# PowerSupplies.net
KiCad netlist of a schematic drawn in Altium Designer
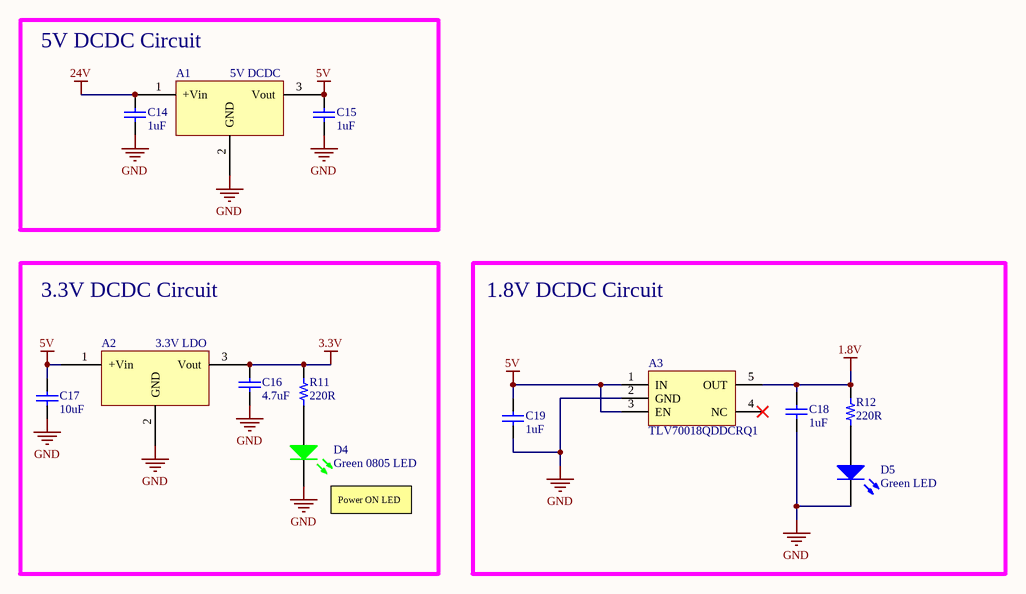
[diagram p0: PowerSupplies.SchDoc]

(export (version "E")
  (design (tool "Eeschema 10.0.6"))
  (components
    (comp (ref "A1")
      (value "5V DCDC")
      (footprint "R-78E-0.5")
      (fields (field (name "MANUFACTURER") "Recom") (field (name "PART_NUMBER") "R-78E5.0-0.5"))
      (libsource (lib "Other") (part "R78E5.0-0.5"))
    )
    (comp (ref "A2")
      (value "3.3V LDO")
      (footprint "TO252-3")
      (description "Linear Voltage Regulator IC Positive Fixed 1 Output 3.3V 500mA DPAK-3")
      (fields (field (name "MANUFACTURER") "ON Semiconductor") (field (name "PART_NUMBER") "NCV5501DT33RKG"))
      (libsource (lib "IC") (part "NCV5501DT33RKG"))
    )
    (comp (ref "A3")
      (value "TLV70018QDDCRQ1")
      (footprint "SOT-23-5")
      (description "Linear Voltage Regulator IC Positive Fixed 1 Output 1.8V 300mA SOT-23-5")
      (fields (field (name "MANUFACTURER") "Texas Instruments"))
      (libsource (lib "IC") (part "TLV70018QDDCRQ1"))
    )
    (comp (ref "C14")
      (value "1uF")
      (footprint "Capacitors:C0603")
      (description "1uF ceramic capacitor")
      (fields (field (name "MANUFACTURER") "TDK Corporation") (field (name "TOLERANCE") "20%"))
      (libsource (lib "Capacitors") (part "CAP CER 0603 1uF 25V X7R 20%"))
    )
    (comp (ref "C15")
      (value "1uF")
      (footprint "Capacitors:C0603")
      (description "1uF ceramic capacitor")
      (fields (field (name "MANUFACTURER") "TDK Corporation") (field (name "TOLERANCE") "20%"))
      (libsource (lib "Capacitors") (part "CAP CER 0603 1uF 25V X7R 20%"))
    )
    (comp (ref "C16")
      (value "4.7uF")
      (footprint "Capacitors:C0603")
      (description "4.7uF ceramic capacitor")
      (fields (field (name "MANUFACTURER") "Kernet") (field (name "TOLERANCE") "10%"))
      (libsource (lib "Capacitors") (part "CAP CER 0603 4.7uF 25V X7R 10%"))
    )
    (comp (ref "C17")
      (value "10uF")
      (footprint "Capacitors:C0603")
      (description "10uF ceramic capacitor")
      (fields (field (name "MANUFACTURER") "Taiyo Yuden") (field (name "TOLERANCE") "20%"))
      (libsource (lib "Capacitors") (part "CAP CER 0603 10uF 6.3V X5R 20%"))
    )
    (comp (ref "C18")
      (value "1uF")
      (footprint "Capacitors:C0603")
      (description "1uF ceramic capacitor")
      (fields (field (name "MANUFACTURER") "Samsung Electro-Mechanics") (field (name "TOLERANCE") "10%"))
      (libsource (lib "Capacitors") (part "CAP CER 0603 1uF 16V X7R 10%"))
    )
    (comp (ref "C19")
      (value "1uF")
      (footprint "Capacitors:C0603")
      (description "1uF ceramic capacitor")
      (fields (field (name "MANUFACTURER") "Samsung Electro-Mechanics") (field (name "TOLERANCE") "10%"))
      (libsource (lib "Capacitors") (part "CAP CER 0603 1uF 16V X7R 10%"))
    )
    (comp (ref "D4")
      (value "Green 0805 LED")
      (footprint "LED0805")
      (description "Green 525nm LED Indication - Discrete 2.65V 0805 (2012 Metric)")
      (fields (field (name "MANUFACTURER") "Kingbright") (field (name "PART_NUMBER") "APT2012LZGCK"))
      (libsource (lib "Diodes") (part "APT2012LZGCK"))
    )
    (comp (ref "D5")
      (value "Green LED")
      (footprint "LED0603")
      (description "Green LED 0603, 2V, 20mA")
      (fields (field (name "MANUFACTURER") "Wurth Electronics") (field (name "PART_NUMBER") "150060VS75000"))
      (libsource (lib "Diodes") (part "150060VS75000"))
    )
    (comp (ref "R11")
      (value "220R")
      (footprint "R0603")
      (description "220 Ohms 0.25W Resistor")
      (fields (field (name "PART_NUMBER") "ESR03EZPJ221") (field (name "MANUFACTURER") "Rohm Semiconductor"))
      (libsource (lib "Resistors") (part "RES 0603 220R 5% 0.25W"))
    )
    (comp (ref "R12")
      (value "220R")
      (footprint "R0603")
      (description "220 Ohms 0.25W Resistor")
      (fields (field (name "PART_NUMBER") "ESR03EZPJ221") (field (name "MANUFACTURER") "Rohm Semiconductor"))
      (libsource (lib "Resistors") (part "RES 0603 220R 5% 0.25W"))
    )
  )
  (nets
    (net (code "1") (name "1.8V") (class "Default")
      (node (ref "A3") (pin "5") (pinfunction "OUT_5") (pintype "passive"))
      (node (ref "C18") (pin "2") (pinfunction "2_2") (pintype "passive"))
      (node (ref "R12") (pin "2") (pinfunction "2_2") (pintype "passive"))
    )
    (net (code "2") (name "3.3V") (class "Default")
      (node (ref "A2") (pin "3") (pinfunction "Vout_3") (pintype "passive"))
      (node (ref "C16") (pin "2") (pinfunction "2_2") (pintype "passive"))
      (node (ref "R11") (pin "2") (pinfunction "2_2") (pintype "passive"))
    )
    (net (code "3") (name "5V") (class "Default")
      (node (ref "A1") (pin "3") (pinfunction "Vout_3") (pintype "passive"))
      (node (ref "A2") (pin "1") (pinfunction "+Vin_1") (pintype "passive"))
      (node (ref "A3") (pin "1") (pinfunction "IN_1") (pintype "passive"))
      (node (ref "A3") (pin "3") (pinfunction "EN_3") (pintype "passive"))
      (node (ref "C15") (pin "2") (pinfunction "2_2") (pintype "passive"))
      (node (ref "C17") (pin "2") (pinfunction "2_2") (pintype "passive"))
      (node (ref "C19") (pin "2") (pinfunction "2_2") (pintype "passive"))
    )
    (net (code "4") (name "24V") (class "Default")
      (node (ref "A1") (pin "1") (pinfunction "+Vin_1") (pintype "passive"))
      (node (ref "C14") (pin "2") (pinfunction "2_2") (pintype "passive"))
    )
    (net (code "5") (name "GND") (class "Default")
      (node (ref "A1") (pin "2") (pinfunction "GND_2") (pintype "passive"))
      (node (ref "A2") (pin "2") (pinfunction "GND_2") (pintype "passive"))
      (node (ref "A3") (pin "2") (pinfunction "GND_2") (pintype "passive"))
      (node (ref "C14") (pin "1") (pinfunction "1_1") (pintype "passive"))
      (node (ref "C15") (pin "1") (pinfunction "1_1") (pintype "passive"))
      (node (ref "C16") (pin "1") (pinfunction "1_1") (pintype "passive"))
      (node (ref "C17") (pin "1") (pinfunction "1_1") (pintype "passive"))
      (node (ref "C18") (pin "1") (pinfunction "1_1") (pintype "passive"))
      (node (ref "C19") (pin "1") (pinfunction "1_1") (pintype "passive"))
      (node (ref "D4") (pin "1") (pinfunction "K_1") (pintype "passive"))
      (node (ref "D5") (pin "1") (pinfunction "K_1") (pintype "passive"))
    )
    (net (code "6") (name "Net-(D4-A)") (class "Default")
      (node (ref "D4") (pin "2") (pinfunction "A_2") (pintype "passive"))
      (node (ref "R11") (pin "1") (pinfunction "1_1") (pintype "passive"))
    )
    (net (code "7") (name "Net-(D5-A)") (class "Default")
      (node (ref "D5") (pin "2") (pinfunction "A_2") (pintype "passive"))
      (node (ref "R12") (pin "1") (pinfunction "1_1") (pintype "passive"))
    )
    (net (code "8") (name "unconnected-(A3-NC-Pad4)") (class "Default")
      (node (ref "A3") (pin "4") (pinfunction "NC_4") (pintype "passive+no_connect"))
    )
  )
)
